# ADC_board_2.net
KiCad netlist of a schematic drawn in EAGLE
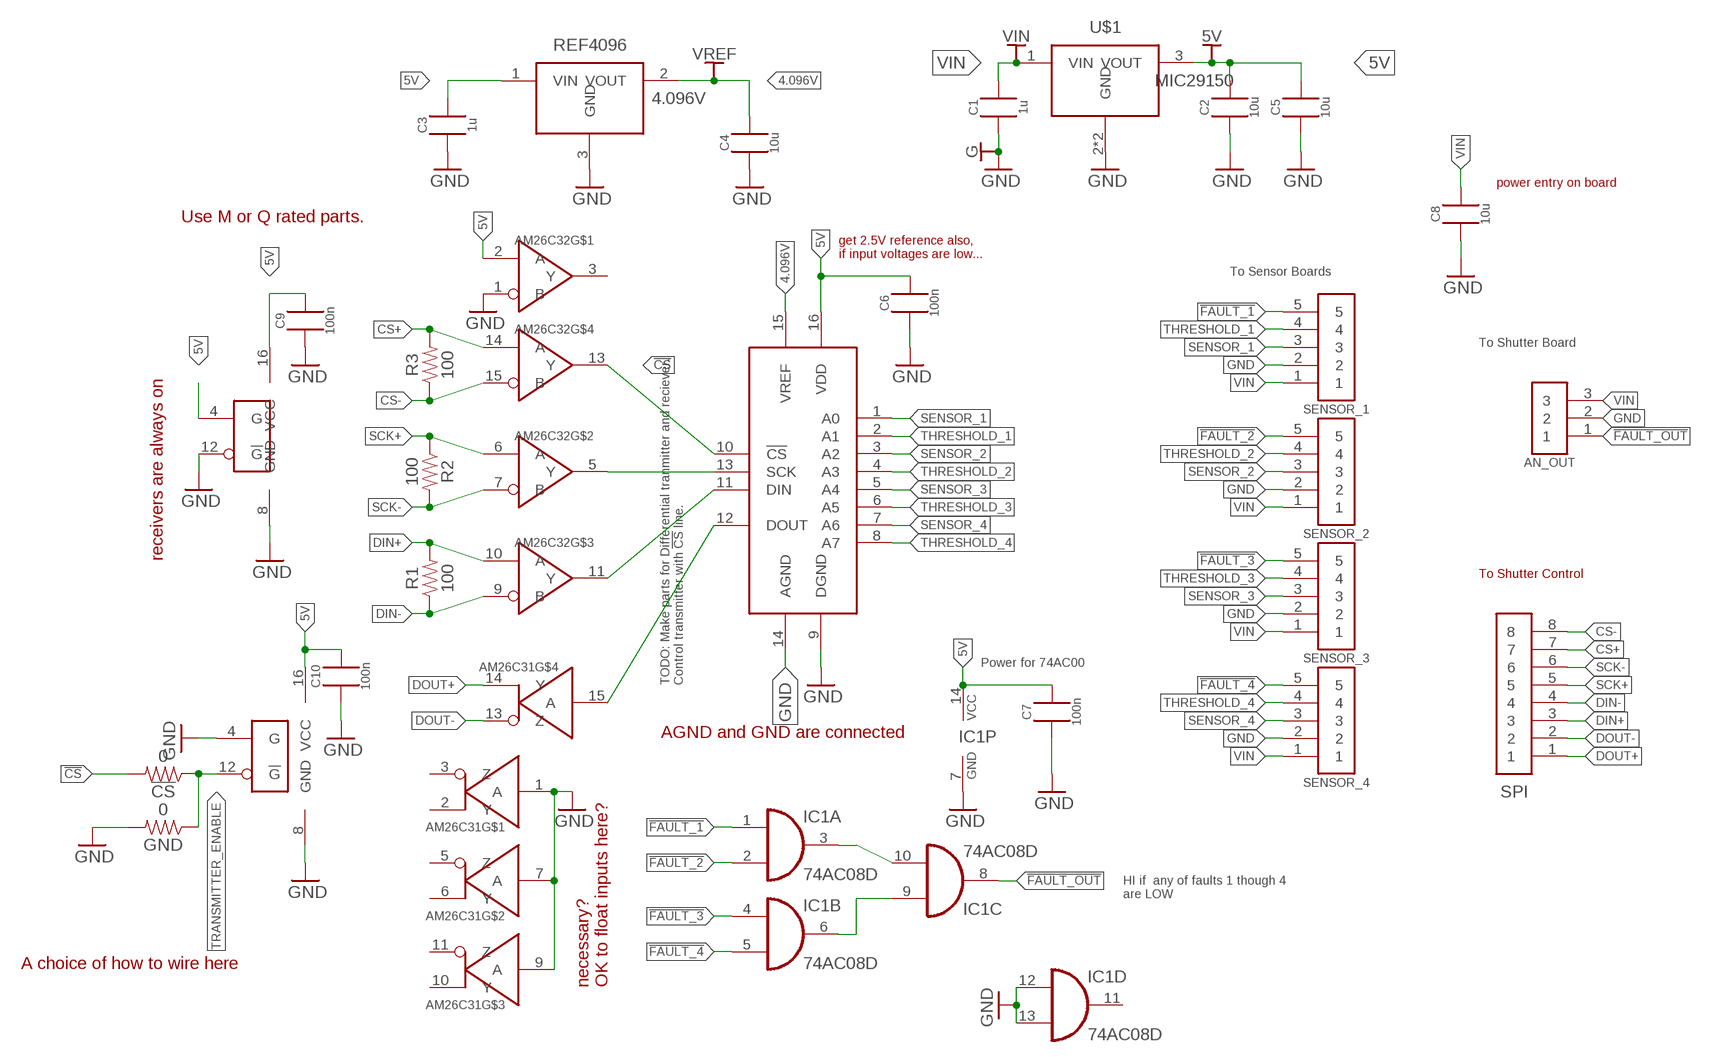
[diagram p0: schematic, sheet 1]

(export (version "E")
  (design (tool "Eeschema 10.0.6"))
  (components
    (comp (ref "!CS!")
      (value "0")
      (footprint "eagle-import:1206")
      (libsource (lib "eagle-import") (part "RESISTOR1206"))
    )
    (comp (ref "5V")
      (value "TEST_POINT5015")
      (footprint "eagle-import:5015")
      (libsource (lib "eagle-import") (part "TEST_POINT5015"))
    )
    (comp (ref "AM26C31")
      (value "AM26C31")
      (footprint "eagle-import:SOIC_16_NARROW")
      (libsource (lib "eagle-import") (part "AM26C31"))
    )
    (comp (ref "AM26C32")
      (value "AM26C32")
      (footprint "eagle-import:SOIC_16_NARROW")
      (libsource (lib "eagle-import") (part "AM26C32"))
    )
    (comp (ref "AN_OUT")
      (value "MO3")
      (footprint "eagle-import:OSTVN03")
      (libsource (lib "eagle-import") (part "MO3"))
    )
    (comp (ref "C1")
      (value "1u")
      (footprint "eagle-import:0805_B")
      (libsource (lib "eagle-import") (part "CAP805B"))
    )
    (comp (ref "C2")
      (value "10u")
      (footprint "eagle-import:1206_A")
      (libsource (lib "eagle-import") (part "CAP1206A"))
    )
    (comp (ref "C3")
      (value "1u")
      (footprint "eagle-import:0805_B")
      (libsource (lib "eagle-import") (part "CAP805B"))
    )
    (comp (ref "C4")
      (value "10u")
      (footprint "eagle-import:1206_A")
      (libsource (lib "eagle-import") (part "CAP1206A"))
    )
    (comp (ref "C5")
      (value "10u")
      (footprint "eagle-import:1206_A")
      (libsource (lib "eagle-import") (part "CAP1206A"))
    )
    (comp (ref "C6")
      (value "100n")
      (footprint "eagle-import:0805_B")
      (libsource (lib "eagle-import") (part "CAP805B"))
    )
    (comp (ref "C7")
      (value "100n")
      (footprint "eagle-import:0805_B")
      (libsource (lib "eagle-import") (part "CAP805B"))
    )
    (comp (ref "C8")
      (value "10u")
      (footprint "eagle-import:1206_A")
      (libsource (lib "eagle-import") (part "CAP1206A"))
    )
    (comp (ref "C9")
      (value "100n")
      (footprint "eagle-import:0805_B")
      (libsource (lib "eagle-import") (part "CAP805B"))
    )
    (comp (ref "C10")
      (value "100n")
      (footprint "eagle-import:0805_B")
      (libsource (lib "eagle-import") (part "CAP805B"))
    )
    (comp (ref "G")
      (value "TEST_POINT5015")
      (footprint "eagle-import:5015")
      (libsource (lib "eagle-import") (part "TEST_POINT5015"))
    )
    (comp (ref "GND")
      (value "0")
      (footprint "eagle-import:1206")
      (libsource (lib "eagle-import") (part "RESISTOR1206"))
    )
    (comp (ref "IC1")
      (value "74AC08D")
      (footprint "eagle-import:SO14")
      (libsource (lib "eagle-import") (part "7408DAC"))
    )
    (comp (ref "MCP3008")
      (value "MCP3008MCP3008")
      (footprint "eagle-import:SOIC-16-NARROW")
      (libsource (lib "eagle-import") (part "MCP3008MCP3008"))
    )
    (comp (ref "R1")
      (value "100")
      (footprint "eagle-import:1206")
      (libsource (lib "eagle-import") (part "RESISTOR1206"))
    )
    (comp (ref "R2")
      (value "100")
      (footprint "eagle-import:1206")
      (libsource (lib "eagle-import") (part "RESISTOR1206"))
    )
    (comp (ref "R3")
      (value "100")
      (footprint "eagle-import:1206")
      (libsource (lib "eagle-import") (part "RESISTOR1206"))
    )
    (comp (ref "REF4096")
      (value "4.096V")
      (footprint "eagle-import:SOT23A(CB)")
      (libsource (lib "eagle-import") (part "MCP1541"))
    )
    (comp (ref "SENSOR_1")
      (value "M05OSTVN05")
      (footprint "eagle-import:OSTVN05")
      (libsource (lib "eagle-import") (part "M05OSTVN05"))
    )
    (comp (ref "SENSOR_2")
      (value "M05OSTVN05")
      (footprint "eagle-import:OSTVN05")
      (libsource (lib "eagle-import") (part "M05OSTVN05"))
    )
    (comp (ref "SENSOR_3")
      (value "M05OSTVN05")
      (footprint "eagle-import:OSTVN05")
      (libsource (lib "eagle-import") (part "M05OSTVN05"))
    )
    (comp (ref "SENSOR_4")
      (value "M05OSTVN05")
      (footprint "eagle-import:OSTVN05")
      (libsource (lib "eagle-import") (part "M05OSTVN05"))
    )
    (comp (ref "SPI")
      (value "M08")
      (footprint "eagle-import:OSTVN08")
      (libsource (lib "eagle-import") (part "M08"))
    )
    (comp (ref "U$1")
      (value "MIC29150")
      (footprint "eagle-import:TO263-3")
      (libsource (lib "eagle-import") (part "MIC29150"))
    )
    (comp (ref "VIN")
      (value "TEST_POINT5015")
      (footprint "eagle-import:5015")
      (libsource (lib "eagle-import") (part "TEST_POINT5015"))
    )
    (comp (ref "VREF")
      (value "TEST_POINT5015")
      (footprint "eagle-import:5015")
      (libsource (lib "eagle-import") (part "TEST_POINT5015"))
    )
  )
  (nets
    (net (code "1") (name "/~{CS}") (class "Default")
      (node (ref "!CS!") (pin "2") (pinfunction "2_2") (pintype "passive"))
      (node (ref "AM26C32") (pin "13") (pinfunction "Y_13") (pintype "output"))
      (node (ref "MCP3008") (pin "10") (pinfunction "~{CS}_10") (pintype "input"))
    )
    (net (code "2") (name "/~{FAULT_1}") (class "Default")
      (node (ref "IC1") (pin "1") (pinfunction "I0_1") (pintype "input"))
      (node (ref "SENSOR_1") (pin "5") (pinfunction "5_5") (pintype "bidirectional"))
    )
    (net (code "3") (name "/~{FAULT_2}") (class "Default")
      (node (ref "IC1") (pin "2") (pinfunction "I1_2") (pintype "input"))
      (node (ref "SENSOR_2") (pin "5") (pinfunction "5_5") (pintype "bidirectional"))
    )
    (net (code "4") (name "/~{FAULT_3}") (class "Default")
      (node (ref "IC1") (pin "4") (pinfunction "I0_4") (pintype "input"))
      (node (ref "SENSOR_3") (pin "5") (pinfunction "5_5") (pintype "bidirectional"))
    )
    (net (code "5") (name "/~{FAULT_4}") (class "Default")
      (node (ref "IC1") (pin "5") (pinfunction "I1_5") (pintype "input"))
      (node (ref "SENSOR_4") (pin "5") (pinfunction "5_5") (pintype "bidirectional"))
    )
    (net (code "6") (name "/~{FAULT_OUT}") (class "Default")
      (node (ref "AN_OUT") (pin "1") (pinfunction "1_1") (pintype "bidirectional"))
      (node (ref "IC1") (pin "8") (pinfunction "O_8") (pintype "output"))
    )
    (net (code "7") (name "4.096V") (class "Default")
      (node (ref "C4") (pin "2") (pinfunction "2_2") (pintype "bidirectional"))
      (node (ref "MCP3008") (pin "15") (pinfunction "VREF_15") (pintype "input"))
      (node (ref "REF4096") (pin "2") (pinfunction "VOUT_2") (pintype "power_in"))
      (node (ref "VREF") (pin "1") (pinfunction "P$1_1") (pintype "bidirectional"))
    )
    (net (code "8") (name "5V") (class "Default")
      (node (ref "5V") (pin "1") (pinfunction "P$1_1") (pintype "bidirectional"))
      (node (ref "AM26C31") (pin "16") (pinfunction "VCC_16") (pintype "power_in"))
      (node (ref "AM26C32") (pin "16") (pinfunction "VCC_16") (pintype "power_in"))
      (node (ref "AM26C32") (pin "2") (pinfunction "A_2") (pintype "input"))
      (node (ref "AM26C32") (pin "4") (pinfunction "G_4") (pintype "input"))
      (node (ref "C10") (pin "2") (pinfunction "2_2") (pintype "bidirectional"))
      (node (ref "C2") (pin "2") (pinfunction "2_2") (pintype "bidirectional"))
      (node (ref "C3") (pin "2") (pinfunction "2_2") (pintype "bidirectional"))
      (node (ref "C5") (pin "2") (pinfunction "2_2") (pintype "bidirectional"))
      (node (ref "C6") (pin "2") (pinfunction "2_2") (pintype "bidirectional"))
      (node (ref "C7") (pin "2") (pinfunction "2_2") (pintype "bidirectional"))
      (node (ref "C9") (pin "2") (pinfunction "2_2") (pintype "bidirectional"))
      (node (ref "IC1") (pin "14") (pinfunction "VCC_14") (pintype "power_in"))
      (node (ref "MCP3008") (pin "16") (pinfunction "VDD_16") (pintype "power_in"))
      (node (ref "REF4096") (pin "1") (pinfunction "VIN_1") (pintype "power_in"))
      (node (ref "U$1") (pin "3") (pinfunction "VOUT_3") (pintype "power_in"))
    )
    (net (code "9") (name "CS+") (class "Default")
      (node (ref "AM26C32") (pin "14") (pinfunction "A_14") (pintype "input"))
      (node (ref "R3") (pin "2") (pinfunction "2_2") (pintype "passive"))
      (node (ref "SPI") (pin "7") (pinfunction "7_7") (pintype "bidirectional"))
    )
    (net (code "10") (name "CS-") (class "Default")
      (node (ref "AM26C32") (pin "15") (pinfunction "B_15") (pintype "input"))
      (node (ref "R3") (pin "1") (pinfunction "1_1") (pintype "passive"))
      (node (ref "SPI") (pin "8") (pinfunction "8_8") (pintype "bidirectional"))
    )
    (net (code "11") (name "DIN+") (class "Default")
      (node (ref "AM26C32") (pin "10") (pinfunction "A_10") (pintype "input"))
      (node (ref "R1") (pin "2") (pinfunction "2_2") (pintype "passive"))
      (node (ref "SPI") (pin "3") (pinfunction "3_3") (pintype "bidirectional"))
    )
    (net (code "12") (name "DIN-") (class "Default")
      (node (ref "AM26C32") (pin "9") (pinfunction "B_9") (pintype "input"))
      (node (ref "R1") (pin "1") (pinfunction "1_1") (pintype "passive"))
      (node (ref "SPI") (pin "4") (pinfunction "4_4") (pintype "bidirectional"))
    )
    (net (code "13") (name "DOUT+") (class "Default")
      (node (ref "AM26C31") (pin "14") (pinfunction "Y_14") (pintype "output"))
      (node (ref "SPI") (pin "1") (pinfunction "1_1") (pintype "bidirectional"))
    )
    (net (code "14") (name "DOUT-") (class "Default")
      (node (ref "AM26C31") (pin "13") (pinfunction "Z_13") (pintype "output"))
      (node (ref "SPI") (pin "2") (pinfunction "2_2") (pintype "bidirectional"))
    )
    (net (code "15") (name "GND") (class "Default")
      (node (ref "AM26C31") (pin "1") (pinfunction "A_1") (pintype "input"))
      (node (ref "AM26C31") (pin "4") (pinfunction "G_4") (pintype "input"))
      (node (ref "AM26C31") (pin "7") (pinfunction "A_7") (pintype "input"))
      (node (ref "AM26C31") (pin "8") (pinfunction "GND_8") (pintype "bidirectional"))
      (node (ref "AM26C31") (pin "9") (pinfunction "A_9") (pintype "input"))
      (node (ref "AM26C32") (pin "1") (pinfunction "B_1") (pintype "input"))
      (node (ref "AM26C32") (pin "12") (pinfunction "~{G}_12") (pintype "input"))
      (node (ref "AM26C32") (pin "8") (pinfunction "GND_8") (pintype "bidirectional"))
      (node (ref "AN_OUT") (pin "2") (pinfunction "2_2") (pintype "bidirectional"))
      (node (ref "C1") (pin "1") (pinfunction "1_1") (pintype "bidirectional"))
      (node (ref "C10") (pin "1") (pinfunction "1_1") (pintype "bidirectional"))
      (node (ref "C2") (pin "1") (pinfunction "1_1") (pintype "bidirectional"))
      (node (ref "C3") (pin "1") (pinfunction "1_1") (pintype "bidirectional"))
      (node (ref "C4") (pin "1") (pinfunction "1_1") (pintype "bidirectional"))
      (node (ref "C5") (pin "1") (pinfunction "1_1") (pintype "bidirectional"))
      (node (ref "C6") (pin "1") (pinfunction "1_1") (pintype "bidirectional"))
      (node (ref "C7") (pin "1") (pinfunction "1_1") (pintype "bidirectional"))
      (node (ref "C8") (pin "1") (pinfunction "1_1") (pintype "bidirectional"))
      (node (ref "C9") (pin "1") (pinfunction "1_1") (pintype "bidirectional"))
      (node (ref "G") (pin "1") (pinfunction "P$1_1") (pintype "bidirectional"))
      (node (ref "GND") (pin "2") (pinfunction "2_2") (pintype "passive"))
      (node (ref "IC1") (pin "12") (pinfunction "I0_12") (pintype "input"))
      (node (ref "IC1") (pin "13") (pinfunction "I1_13") (pintype "input"))
      (node (ref "IC1") (pin "7") (pinfunction "GND_7") (pintype "power_in"))
      (node (ref "MCP3008") (pin "14") (pinfunction "AGND_14") (pintype "power_in"))
      (node (ref "MCP3008") (pin "9") (pinfunction "DGND_9") (pintype "power_in"))
      (node (ref "REF4096") (pin "3") (pinfunction "GND_3") (pintype "power_in"))
      (node (ref "SENSOR_1") (pin "2") (pinfunction "2_2") (pintype "bidirectional"))
      (node (ref "SENSOR_2") (pin "2") (pinfunction "2_2") (pintype "bidirectional"))
      (node (ref "SENSOR_3") (pin "2") (pinfunction "2_2") (pintype "bidirectional"))
      (node (ref "SENSOR_4") (pin "2") (pinfunction "2_2") (pintype "bidirectional"))
      (node (ref "U$1") (pin "2") (pinfunction "GND_2") (pintype "power_in"))
      (node (ref "U$1") (pin "P$3") (pinfunction "GND_P$3") (pintype "power_in"))
    )
    (net (code "16") (name "Net-(AM26C31D-A)") (class "Default")
      (node (ref "AM26C31") (pin "15") (pinfunction "A_15") (pintype "input"))
      (node (ref "MCP3008") (pin "12") (pinfunction "DOUT_12") (pintype "output"))
    )
    (net (code "17") (name "Net-(AM26C32B-Y)") (class "Default")
      (node (ref "AM26C32") (pin "5") (pinfunction "Y_5") (pintype "output"))
      (node (ref "MCP3008") (pin "13") (pinfunction "SCK_13") (pintype "input"))
    )
    (net (code "18") (name "Net-(AM26C32C-Y)") (class "Default")
      (node (ref "AM26C32") (pin "11") (pinfunction "Y_11") (pintype "output"))
      (node (ref "MCP3008") (pin "11") (pinfunction "DIN_11") (pintype "input"))
    )
    (net (code "19") (name "Net-(IC1A-O)") (class "Default")
      (node (ref "IC1") (pin "10") (pinfunction "I1_10") (pintype "input"))
      (node (ref "IC1") (pin "3") (pinfunction "O_3") (pintype "output"))
    )
    (net (code "20") (name "Net-(IC1B-O)") (class "Default")
      (node (ref "IC1") (pin "6") (pinfunction "O_6") (pintype "output"))
      (node (ref "IC1") (pin "9") (pinfunction "I0_9") (pintype "input"))
    )
    (net (code "21") (name "SCK+") (class "Default")
      (node (ref "AM26C32") (pin "6") (pinfunction "A_6") (pintype "input"))
      (node (ref "R2") (pin "1") (pinfunction "1_1") (pintype "passive"))
      (node (ref "SPI") (pin "5") (pinfunction "5_5") (pintype "bidirectional"))
    )
    (net (code "22") (name "SCK-") (class "Default")
      (node (ref "AM26C32") (pin "7") (pinfunction "B_7") (pintype "input"))
      (node (ref "R2") (pin "2") (pinfunction "2_2") (pintype "passive"))
      (node (ref "SPI") (pin "6") (pinfunction "6_6") (pintype "bidirectional"))
    )
    (net (code "23") (name "SENSOR_1") (class "Default")
      (node (ref "MCP3008") (pin "1") (pinfunction "A0_1") (pintype "input"))
      (node (ref "SENSOR_1") (pin "3") (pinfunction "3_3") (pintype "bidirectional"))
    )
    (net (code "24") (name "SENSOR_2") (class "Default")
      (node (ref "MCP3008") (pin "3") (pinfunction "A2_3") (pintype "input"))
      (node (ref "SENSOR_2") (pin "3") (pinfunction "3_3") (pintype "bidirectional"))
    )
    (net (code "25") (name "SENSOR_3") (class "Default")
      (node (ref "MCP3008") (pin "5") (pinfunction "A4_5") (pintype "input"))
      (node (ref "SENSOR_3") (pin "3") (pinfunction "3_3") (pintype "bidirectional"))
    )
    (net (code "26") (name "SENSOR_4") (class "Default")
      (node (ref "MCP3008") (pin "7") (pinfunction "A6_7") (pintype "input"))
      (node (ref "SENSOR_4") (pin "3") (pinfunction "3_3") (pintype "bidirectional"))
    )
    (net (code "27") (name "THRESHOLD_1") (class "Default")
      (node (ref "MCP3008") (pin "2") (pinfunction "A1_2") (pintype "input"))
      (node (ref "SENSOR_1") (pin "4") (pinfunction "4_4") (pintype "bidirectional"))
    )
    (net (code "28") (name "THRESHOLD_2") (class "Default")
      (node (ref "MCP3008") (pin "4") (pinfunction "A3_4") (pintype "input"))
      (node (ref "SENSOR_2") (pin "4") (pinfunction "4_4") (pintype "bidirectional"))
    )
    (net (code "29") (name "THRESHOLD_3") (class "Default")
      (node (ref "MCP3008") (pin "6") (pinfunction "A5_6") (pintype "input"))
      (node (ref "SENSOR_3") (pin "4") (pinfunction "4_4") (pintype "bidirectional"))
    )
    (net (code "30") (name "THRESHOLD_4") (class "Default")
      (node (ref "MCP3008") (pin "8") (pinfunction "A7_8") (pintype "input"))
      (node (ref "SENSOR_4") (pin "4") (pinfunction "4_4") (pintype "bidirectional"))
    )
    (net (code "31") (name "TRANSMITTER_ENABLE") (class "Default")
      (node (ref "!CS!") (pin "1") (pinfunction "1_1") (pintype "passive"))
      (node (ref "AM26C31") (pin "12") (pinfunction "~{G}_12") (pintype "input"))
      (node (ref "GND") (pin "1") (pinfunction "1_1") (pintype "passive"))
    )
    (net (code "32") (name "VIN") (class "Default")
      (node (ref "AN_OUT") (pin "3") (pinfunction "3_3") (pintype "bidirectional"))
      (node (ref "C1") (pin "2") (pinfunction "2_2") (pintype "bidirectional"))
      (node (ref "C8") (pin "2") (pinfunction "2_2") (pintype "bidirectional"))
      (node (ref "SENSOR_1") (pin "1") (pinfunction "1_1") (pintype "bidirectional"))
      (node (ref "SENSOR_2") (pin "1") (pinfunction "1_1") (pintype "bidirectional"))
      (node (ref "SENSOR_3") (pin "1") (pinfunction "1_1") (pintype "bidirectional"))
      (node (ref "SENSOR_4") (pin "1") (pinfunction "1_1") (pintype "bidirectional"))
      (node (ref "U$1") (pin "1") (pinfunction "VIN_1") (pintype "power_in"))
      (node (ref "VIN") (pin "1") (pinfunction "P$1_1") (pintype "bidirectional"))
    )
    (net (code "33") (name "unconnected-(AM26C31A-Y-Pad2)") (class "Default")
      (node (ref "AM26C31") (pin "2") (pinfunction "Y_2") (pintype "output"))
    )
    (net (code "34") (name "unconnected-(AM26C31A-Z-Pad3)") (class "Default")
      (node (ref "AM26C31") (pin "3") (pinfunction "Z_3") (pintype "output"))
    )
    (net (code "35") (name "unconnected-(AM26C31B-Y-Pad6)") (class "Default")
      (node (ref "AM26C31") (pin "6") (pinfunction "Y_6") (pintype "output"))
    )
    (net (code "36") (name "unconnected-(AM26C31B-Z-Pad5)") (class "Default")
      (node (ref "AM26C31") (pin "5") (pinfunction "Z_5") (pintype "output"))
    )
    (net (code "37") (name "unconnected-(AM26C31C-Y-Pad10)") (class "Default")
      (node (ref "AM26C31") (pin "10") (pinfunction "Y_10") (pintype "output"))
    )
    (net (code "38") (name "unconnected-(AM26C31C-Z-Pad11)") (class "Default")
      (node (ref "AM26C31") (pin "11") (pinfunction "Z_11") (pintype "output"))
    )
    (net (code "39") (name "unconnected-(AM26C32A-Y-Pad3)") (class "Default")
      (node (ref "AM26C32") (pin "3") (pinfunction "Y_3") (pintype "output"))
    )
    (net (code "40") (name "unconnected-(IC1D-O-Pad11)") (class "Default")
      (node (ref "IC1") (pin "11") (pinfunction "O_11") (pintype "output"))
    )
  )
)
